# SparkFun_AzureWave_Module_Thing_Plus_AW-.net
KiCad netlist of a schematic drawn in EAGLE
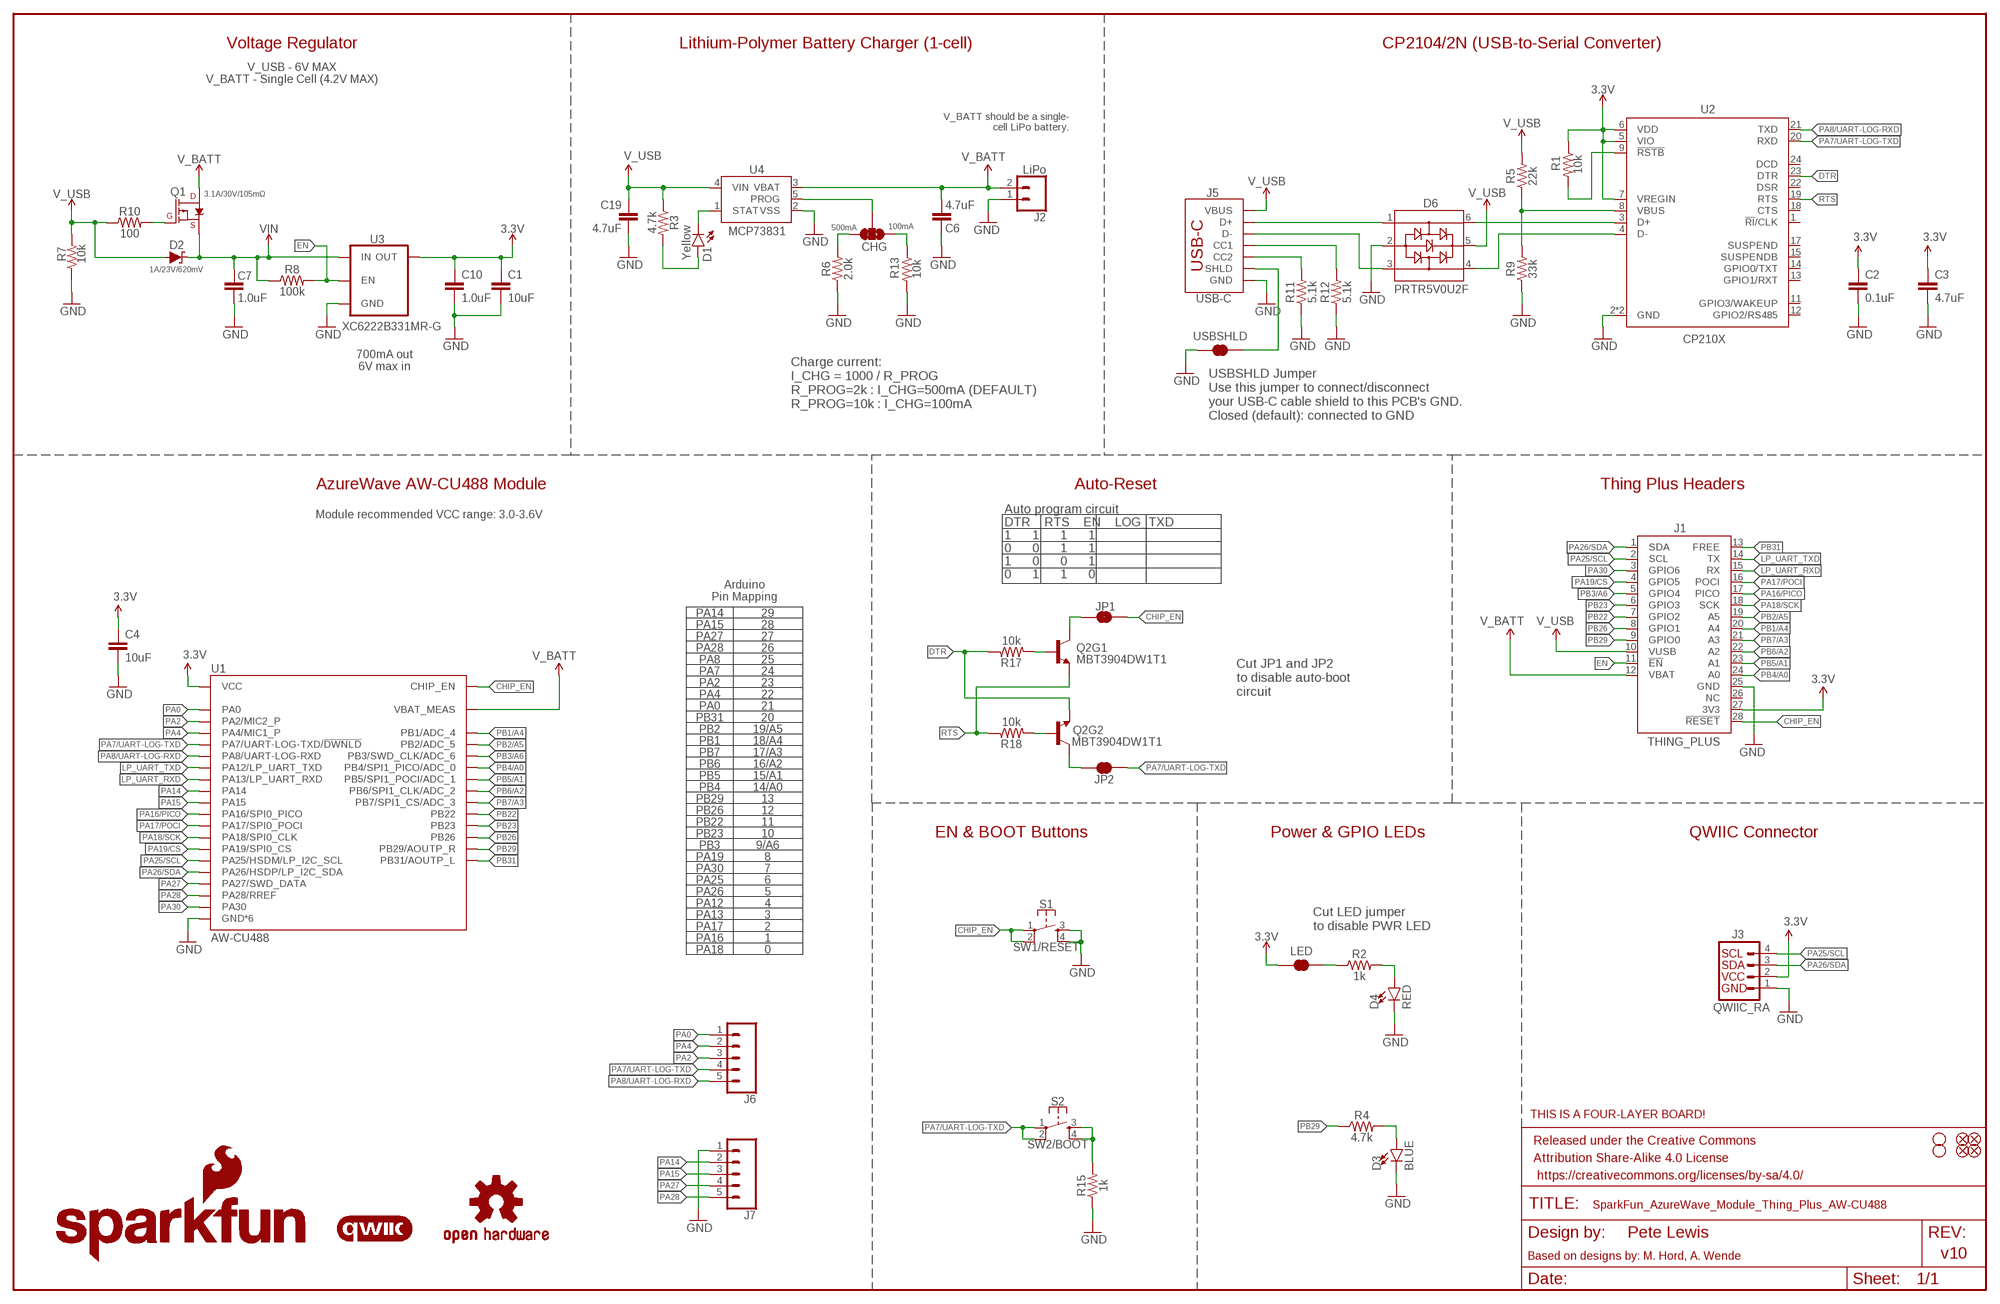
[diagram p0: schematic, sheet 1]

(export (version "E")
  (design (tool "Eeschema 10.0.6"))
  (components
    (comp (ref "C1")
      (value "10uF")
      (footprint "eagle-import:0402-TIGHT")
      (libsource (lib "eagle-import") (part "10UF-0402T-6.3V-20%"))
    )
    (comp (ref "C2")
      (value "0.1uF")
      (footprint "eagle-import:0402-TIGHT")
      (libsource (lib "eagle-import") (part "0.1UF-0402T-16V-10%"))
    )
    (comp (ref "C3")
      (value "4.7uF")
      (footprint "eagle-import:0402-TIGHT")
      (libsource (lib "eagle-import") (part "4.7UF-0402_TIGHT-6.3V-20%-X5R"))
    )
    (comp (ref "C4")
      (value "10uF")
      (footprint "eagle-import:0603")
      (libsource (lib "eagle-import") (part "10UF-0603-6.3V-20%"))
    )
    (comp (ref "C6")
      (value "4.7uF")
      (footprint "eagle-import:0402-TIGHT")
      (libsource (lib "eagle-import") (part "4.7UF-0402_TIGHT-6.3V-20%-X5R"))
    )
    (comp (ref "C7")
      (value "1.0uF")
      (footprint "eagle-import:0402-TIGHT")
      (libsource (lib "eagle-import") (part "1.0UF-0402T-16V-10%"))
    )
    (comp (ref "C10")
      (value "1.0uF")
      (footprint "eagle-import:0402-TIGHT")
      (libsource (lib "eagle-import") (part "1.0UF-0402T-16V-10%"))
    )
    (comp (ref "C19")
      (value "4.7uF")
      (footprint "eagle-import:0402-TIGHT")
      (libsource (lib "eagle-import") (part "4.7UF-0402_TIGHT-6.3V-20%-X5R"))
    )
    (comp (ref "CHG")
      (value "JUMPER-SMT_3_1-NC_TRACE_SILK")
      (footprint "eagle-import:SMT-JUMPER_3_1-NC_TRACE_SILK")
      (libsource (lib "eagle-import") (part "JUMPER-SMT_3_1-NC_TRACE_SILK"))
    )
    (comp (ref "D1")
      (value "Yellow")
      (footprint "eagle-import:LED-0603")
      (libsource (lib "eagle-import") (part "LED-YELLOW0603"))
    )
    (comp (ref "D2")
      (value "1A/23V/620mV")
      (footprint "eagle-import:SOD-323")
      (libsource (lib "eagle-import") (part "DIODE-SCHOTTKY-BAT20J"))
    )
    (comp (ref "D3")
      (value "BLUE")
      (footprint "eagle-import:LED-0603")
      (libsource (lib "eagle-import") (part "LED-BLUE0603"))
    )
    (comp (ref "D4")
      (value "RED")
      (footprint "eagle-import:LED-0603")
      (libsource (lib "eagle-import") (part "LED-RED0603"))
    )
    (comp (ref "D6")
      (value "PRTR5V0U2F")
      (footprint "eagle-import:SOT886")
      (libsource (lib "eagle-import") (part "PRTR5V0U2F"))
    )
    (comp (ref "FD1")
      (value "FIDUCIALUFIDUCIAL")
      (footprint "eagle-import:FIDUCIAL-MICRO")
      (libsource (lib "eagle-import") (part "FIDUCIALUFIDUCIAL"))
    )
    (comp (ref "FD2")
      (value "FIDUCIALUFIDUCIAL")
      (footprint "eagle-import:FIDUCIAL-MICRO")
      (libsource (lib "eagle-import") (part "FIDUCIALUFIDUCIAL"))
    )
    (comp (ref "FD3")
      (value "FIDUCIALUFIDUCIAL")
      (footprint "eagle-import:FIDUCIAL-MICRO")
      (libsource (lib "eagle-import") (part "FIDUCIALUFIDUCIAL"))
    )
    (comp (ref "FD4")
      (value "FIDUCIALUFIDUCIAL")
      (footprint "eagle-import:FIDUCIAL-MICRO")
      (libsource (lib "eagle-import") (part "FIDUCIALUFIDUCIAL"))
    )
    (comp (ref "FRAME1")
      (value "FRAME-LEDGER")
      (footprint "eagle-import:CREATIVE_COMMONS")
      (libsource (lib "eagle-import") (part "FRAME-LEDGER"))
    )
    (comp (ref "H1")
      (value "STAND-OFF")
      (footprint "eagle-import:STAND-OFF")
      (libsource (lib "eagle-import") (part "STAND-OFF"))
    )
    (comp (ref "H2")
      (value "STAND-OFF")
      (footprint "eagle-import:STAND-OFF")
      (libsource (lib "eagle-import") (part "STAND-OFF"))
    )
    (comp (ref "J1")
      (value "THING_PLUS")
      (footprint "eagle-import:THING_PLUS")
      (libsource (lib "eagle-import") (part "THING_PLUS"))
    )
    (comp (ref "J2")
      (value "LiPo")
      (footprint "eagle-import:JST-2-SMD")
      (libsource (lib "eagle-import") (part "CONN_02-JST-2MM-SMT"))
    )
    (comp (ref "J3")
      (value "QWIIC_RA")
      (footprint "eagle-import:JST04_1MM_RA")
      (libsource (lib "eagle-import") (part "QWIIC_CONNECTORJS-1MM"))
    )
    (comp (ref "J5")
      (value "USB-C")
      (footprint "eagle-import:USB-C-16P-4LAYER-ISOLATED")
      (libsource (lib "eagle-import") (part "USB_C_4-LAYER-ISOLATED"))
    )
    (comp (ref "J6")
      (value "CONN_05NO_SILK")
      (footprint "eagle-import:1X05_NO_SILK")
      (libsource (lib "eagle-import") (part "CONN_05NO_SILK"))
    )
    (comp (ref "J7")
      (value "CONN_05NO_SILK")
      (footprint "eagle-import:1X05_NO_SILK")
      (libsource (lib "eagle-import") (part "CONN_05NO_SILK"))
    )
    (comp (ref "JP1")
      (value "JUMPER-SMT_2_NC_TRACE_SILK")
      (footprint "eagle-import:SMT-JUMPER_2_NC_TRACE_SILK")
      (libsource (lib "eagle-import") (part "JUMPER-SMT_2_NC_TRACE_SILK"))
    )
    (comp (ref "JP2")
      (value "JUMPER-SMT_2_NC_TRACE_SILK")
      (footprint "eagle-import:SMT-JUMPER_2_NC_TRACE_SILK")
      (libsource (lib "eagle-import") (part "JUMPER-SMT_2_NC_TRACE_SILK"))
    )
    (comp (ref "LED")
      (value "JUMPER-SMT_2_NC_TRACE_SILK")
      (footprint "eagle-import:SMT-JUMPER_2_NC_TRACE_SILK")
      (libsource (lib "eagle-import") (part "JUMPER-SMT_2_NC_TRACE_SILK"))
    )
    (comp (ref "LOGO1")
      (value "SFE_LOGO_NAME.1_INCH")
      (footprint "eagle-import:SFE_LOGO_NAME_.1")
      (libsource (lib "eagle-import") (part "SFE_LOGO_NAME.1_INCH"))
    )
    (comp (ref "LOGO2")
      (value "OSHW-LOGOMINI")
      (footprint "eagle-import:OSHW-LOGO-MINI")
      (libsource (lib "eagle-import") (part "OSHW-LOGOMINI"))
    )
    (comp (ref "LOGO3")
      (value "SFE_LOGO_NAME_FLAME.1_INCH")
      (footprint "eagle-import:SFE_LOGO_NAME_FLAME_.1")
      (libsource (lib "eagle-import") (part "SFE_LOGO_NAME_FLAME.1_INCH"))
    )
    (comp (ref "LOGO4")
      (value "FOUR_LAYER_WARNING")
      (footprint "eagle-import:FOUR_LAYER_WARNING")
      (libsource (lib "eagle-import") (part "FOUR_LAYER_WARNING"))
    )
    (comp (ref "LOGO6")
      (value "QWIIC_LOGO_4MM")
      (footprint "eagle-import:QWIIC_4MM")
      (libsource (lib "eagle-import") (part "QWIIC_LOGO_4MM"))
    )
    (comp (ref "Q1")
      (value "3.1A/30V/105mΩ")
      (footprint "eagle-import:SOT23-3")
      (libsource (lib "eagle-import") (part "MOSFET_PCH-DMG2307L"))
    )
    (comp (ref "Q2")
      (value "MBT3904DW1T1")
      (footprint "eagle-import:SC70-6")
      (libsource (lib "eagle-import") (part "TRANS_NPN_DUAL-MBT3904DW1T1"))
    )
    (comp (ref "R1")
      (value "10k")
      (footprint "eagle-import:0402-TIGHT")
      (libsource (lib "eagle-import") (part "10KOHM-0402T-1/16W-1%"))
    )
    (comp (ref "R2")
      (value "1k")
      (footprint "eagle-import:0402-TIGHT")
      (libsource (lib "eagle-import") (part "1KOHM-0402T-1/16W-1%"))
    )
    (comp (ref "R3")
      (value "4.7k")
      (footprint "eagle-import:0402-TIGHT")
      (libsource (lib "eagle-import") (part "4.7KOHM-0402T-1/16W-1%"))
    )
    (comp (ref "R4")
      (value "4.7k")
      (footprint "eagle-import:0402-TIGHT")
      (libsource (lib "eagle-import") (part "4.7KOHM-0402T-1/16W-1%"))
    )
    (comp (ref "R5")
      (value "22k")
      (footprint "eagle-import:0402-TIGHT")
      (libsource (lib "eagle-import") (part "22KOHM-0402_TIGHT-1/10W-1%"))
    )
    (comp (ref "R6")
      (value "2.0k")
      (footprint "eagle-import:0603")
      (libsource (lib "eagle-import") (part "2.0KOHM-0603-1/10W-5%"))
    )
    (comp (ref "R7")
      (value "10k")
      (footprint "eagle-import:0402-TIGHT")
      (libsource (lib "eagle-import") (part "10KOHM-0402T-1/16W-1%"))
    )
    (comp (ref "R8")
      (value "100k")
      (footprint "eagle-import:0402-TIGHT")
      (libsource (lib "eagle-import") (part "100KOHM-0402T-1/16W-1%"))
    )
    (comp (ref "R9")
      (value "33k")
      (footprint "eagle-import:0402-TIGHT")
      (libsource (lib "eagle-import") (part "33KOHM-0402T-1/16W-1%"))
    )
    (comp (ref "R10")
      (value "100")
      (footprint "eagle-import:0402-TIGHT")
      (libsource (lib "eagle-import") (part "100OHM-0402-TIGHT-1/16W-1%"))
    )
    (comp (ref "R11")
      (value "5.1k")
      (footprint "eagle-import:0402-TIGHT")
      (libsource (lib "eagle-import") (part "5.1KOHM-0402T-1/16W-1%"))
    )
    (comp (ref "R12")
      (value "5.1k")
      (footprint "eagle-import:0402-TIGHT")
      (libsource (lib "eagle-import") (part "5.1KOHM-0402T-1/16W-1%"))
    )
    (comp (ref "R13")
      (value "10k")
      (footprint "eagle-import:0402-TIGHT")
      (libsource (lib "eagle-import") (part "10KOHM-0402T-1/16W-1%"))
    )
    (comp (ref "R15")
      (value "1k")
      (footprint "eagle-import:0402-TIGHT")
      (libsource (lib "eagle-import") (part "1KOHM-0402T-1/16W-1%"))
    )
    (comp (ref "R17")
      (value "10k")
      (footprint "eagle-import:0402-TIGHT")
      (libsource (lib "eagle-import") (part "10KOHM-0402T-1/16W-1%"))
    )
    (comp (ref "R18")
      (value "10k")
      (footprint "eagle-import:0402-TIGHT")
      (libsource (lib "eagle-import") (part "10KOHM-0402T-1/16W-1%"))
    )
    (comp (ref "S1")
      (value "SW1/RESET")
      (footprint "eagle-import:TACTILE_SWITCH_SMD_4.6X2.8MM")
      (libsource (lib "eagle-import") (part "MOMENTARY-SWITCH-SPST-2-SMD-4.6X2.8MM"))
    )
    (comp (ref "S2")
      (value "SW2/BOOT")
      (footprint "eagle-import:TACTILE_SWITCH_SMD_4.6X2.8MM")
      (libsource (lib "eagle-import") (part "MOMENTARY-SWITCH-SPST-2-SMD-4.6X2.8MM"))
    )
    (comp (ref "U1")
      (value "AW-CU488")
      (footprint "eagle-import:LGA150_AW-CU488")
      (libsource (lib "eagle-import") (part "AW-CU488LGA150"))
    )
    (comp (ref "U2")
      (value "CP210X")
      (footprint "eagle-import:QFN24")
      (libsource (lib "eagle-import") (part "CP2102N"))
    )
    (comp (ref "U3")
      (value "XC6222B331MR-G")
      (footprint "eagle-import:SOT23-5")
      (libsource (lib "eagle-import") (part "XC6222B331MR-G"))
    )
    (comp (ref "U4")
      (value "MCP73831")
      (footprint "eagle-import:SOT23-5")
      (libsource (lib "eagle-import") (part "MCP73831"))
    )
    (comp (ref "USBSHLD")
      (value "JUMPER-SMT_2_NC_TRACE_SILK")
      (footprint "eagle-import:SMT-JUMPER_2_NC_TRACE_SILK")
      (libsource (lib "eagle-import") (part "JUMPER-SMT_2_NC_TRACE_SILK"))
    )
  )
  (nets
    (net (code "1") (name "3.3V") (class "Default")
      (node (ref "C1") (pin "1") (pinfunction "1_1") (pintype "passive"))
      (node (ref "C10") (pin "1") (pinfunction "1_1") (pintype "passive"))
      (node (ref "C2") (pin "1") (pinfunction "1_1") (pintype "passive"))
      (node (ref "C3") (pin "1") (pinfunction "1_1") (pintype "passive"))
      (node (ref "C4") (pin "1") (pinfunction "1_1") (pintype "passive"))
      (node (ref "J1") (pin "27") (pinfunction "3V3_27") (pintype "bidirectional"))
      (node (ref "J3") (pin "2") (pinfunction "2_2") (pintype "power_in"))
      (node (ref "LED") (pin "1") (pinfunction "1_1") (pintype "passive"))
      (node (ref "R1") (pin "1") (pinfunction "1_1") (pintype "passive"))
      (node (ref "U1") (pin "F1") (pinfunction "VCC_F1") (pintype "bidirectional"))
      (node (ref "U2") (pin "5") (pinfunction "VIO_5") (pintype "bidirectional"))
      (node (ref "U2") (pin "6") (pinfunction "VDD_6") (pintype "bidirectional"))
      (node (ref "U2") (pin "7") (pinfunction "VREGIN_7") (pintype "bidirectional"))
      (node (ref "U3") (pin "5") (pinfunction "OUT_5") (pintype "passive"))
    )
    (net (code "2") (name "CHIP_EN") (class "Default")
      (node (ref "J1") (pin "28") (pinfunction "~{RESET}_28") (pintype "bidirectional"))
      (node (ref "JP1") (pin "2") (pinfunction "2_2") (pintype "passive"))
      (node (ref "S1") (pin "1") (pinfunction "1_1") (pintype "passive"))
      (node (ref "S1") (pin "2") (pinfunction "2_2") (pintype "passive"))
      (node (ref "U1") (pin "K11") (pinfunction "CHIP_EN_K11") (pintype "bidirectional"))
    )
    (net (code "3") (name "DTR") (class "Default")
      (node (ref "Q2") (pin "1") (pinfunction "E_1") (pintype "passive"))
      (node (ref "R17") (pin "1") (pinfunction "1_1") (pintype "passive"))
      (node (ref "U2") (pin "23") (pinfunction "DTR_23") (pintype "bidirectional"))
    )
    (net (code "4") (name "EN") (class "Default")
      (node (ref "J1") (pin "11") (pinfunction "~{EN}_11") (pintype "bidirectional"))
      (node (ref "R8") (pin "2") (pinfunction "2_2") (pintype "passive"))
      (node (ref "U3") (pin "3") (pinfunction "EN_3") (pintype "input"))
    )
    (net (code "5") (name "GND") (class "Default")
      (node (ref "C1") (pin "2") (pinfunction "2_2") (pintype "passive"))
      (node (ref "C10") (pin "2") (pinfunction "2_2") (pintype "passive"))
      (node (ref "C19") (pin "2") (pinfunction "2_2") (pintype "passive"))
      (node (ref "C2") (pin "2") (pinfunction "2_2") (pintype "passive"))
      (node (ref "C3") (pin "2") (pinfunction "2_2") (pintype "passive"))
      (node (ref "C4") (pin "2") (pinfunction "2_2") (pintype "passive"))
      (node (ref "C6") (pin "2") (pinfunction "2_2") (pintype "passive"))
      (node (ref "C7") (pin "2") (pinfunction "2_2") (pintype "passive"))
      (node (ref "D3") (pin "C") (pinfunction "C_C") (pintype "passive"))
      (node (ref "D4") (pin "C") (pinfunction "C_C") (pintype "passive"))
      (node (ref "D6") (pin "2") (pinfunction "2_2") (pintype "power_in"))
      (node (ref "J1") (pin "25") (pinfunction "GND_25") (pintype "bidirectional"))
      (node (ref "J2") (pin "1") (pinfunction "2_1") (pintype "passive"))
      (node (ref "J3") (pin "1") (pinfunction "1_1") (pintype "power_in"))
      (node (ref "J5") (pin "GND") (pinfunction "GND_GND") (pintype "bidirectional"))
      (node (ref "J5") (pin "GND2") (pinfunction "GND_GND2") (pintype "bidirectional"))
      (node (ref "J7") (pin "1") (pinfunction "1_1") (pintype "passive"))
      (node (ref "R11") (pin "1") (pinfunction "1_1") (pintype "passive"))
      (node (ref "R12") (pin "1") (pinfunction "1_1") (pintype "passive"))
      (node (ref "R13") (pin "2") (pinfunction "2_2") (pintype "passive"))
      (node (ref "R15") (pin "1") (pinfunction "1_1") (pintype "passive"))
      (node (ref "R6") (pin "1") (pinfunction "1_1") (pintype "passive"))
      (node (ref "R7") (pin "1") (pinfunction "1_1") (pintype "passive"))
      (node (ref "R9") (pin "1") (pinfunction "1_1") (pintype "passive"))
      (node (ref "S1") (pin "3") (pinfunction "3_3") (pintype "passive"))
      (node (ref "S1") (pin "4") (pinfunction "4_4") (pintype "passive"))
      (node (ref "U1") (pin "A1") (pinfunction "GND*6_A1") (pintype "bidirectional"))
      (node (ref "U1") (pin "A14") (pinfunction "GND*6_A14") (pintype "bidirectional"))
      (node (ref "U1") (pin "A15") (pinfunction "GND*6_A15") (pintype "bidirectional"))
      (node (ref "U1") (pin "A2") (pinfunction "GND*6_A2") (pintype "bidirectional"))
      (node (ref "U1") (pin "B14") (pinfunction "GND*6_B14") (pintype "bidirectional"))
      (node (ref "U1") (pin "B15") (pinfunction "GND*6_B15") (pintype "bidirectional"))
      (node (ref "U1") (pin "C10") (pinfunction "GND*6_C10") (pintype "bidirectional"))
      (node (ref "U1") (pin "C11") (pinfunction "GND*6_C11") (pintype "bidirectional"))
      (node (ref "U1") (pin "C12") (pinfunction "GND*6_C12") (pintype "bidirectional"))
      (node (ref "U1") (pin "C13") (pinfunction "GND*6_C13") (pintype "bidirectional"))
      (node (ref "U1") (pin "C14") (pinfunction "GND*6_C14") (pintype "bidirectional"))
      (node (ref "U1") (pin "C15") (pinfunction "GND*6_C15") (pintype "bidirectional"))
      (node (ref "U1") (pin "C3") (pinfunction "GND*6_C3") (pintype "bidirectional"))
      (node (ref "U1") (pin "C4") (pinfunction "GND*6_C4") (pintype "bidirectional"))
      (node (ref "U1") (pin "C5") (pinfunction "GND*6_C5") (pintype "bidirectional"))
      (node (ref "U1") (pin "C6") (pinfunction "GND*6_C6") (pintype "bidirectional"))
      (node (ref "U1") (pin "C7") (pinfunction "GND*6_C7") (pintype "bidirectional"))
      (node (ref "U1") (pin "C8") (pinfunction "GND*6_C8") (pintype "bidirectional"))
      (node (ref "U1") (pin "C9") (pinfunction "GND*6_C9") (pintype "bidirectional"))
      (node (ref "U1") (pin "D10") (pinfunction "GND*6_D10") (pintype "bidirectional"))
      (node (ref "U1") (pin "D11") (pinfunction "GND*6_D11") (pintype "bidirectional"))
      (node (ref "U1") (pin "D12") (pinfunction "GND*6_D12") (pintype "bidirectional"))
      (node (ref "U1") (pin "D13") (pinfunction "GND*6_D13") (pintype "bidirectional"))
      (node (ref "U1") (pin "D14") (pinfunction "GND*6_D14") (pintype "bidirectional"))
      (node (ref "U1") (pin "D15") (pinfunction "GND*6_D15") (pintype "bidirectional"))
      (node (ref "U1") (pin "D3") (pinfunction "GND*6_D3") (pintype "bidirectional"))
      (node (ref "U1") (pin "D4") (pinfunction "GND*6_D4") (pintype "bidirectional"))
      (node (ref "U1") (pin "D5") (pinfunction "GND*6_D5") (pintype "bidirectional"))
      (node (ref "U1") (pin "D6") (pinfunction "GND*6_D6") (pintype "bidirectional"))
      (node (ref "U1") (pin "D7") (pinfunction "GND*6_D7") (pintype "bidirectional"))
      (node (ref "U1") (pin "D8") (pinfunction "GND*6_D8") (pintype "bidirectional"))
      (node (ref "U1") (pin "D9") (pinfunction "GND*6_D9") (pintype "bidirectional"))
      (node (ref "U1") (pin "E1") (pinfunction "GND*6_E1") (pintype "bidirectional"))
      (node (ref "U1") (pin "E10") (pinfunction "GND*6_E10") (pintype "bidirectional"))
      (node (ref "U1") (pin "E11") (pinfunction "GND*6_E11") (pintype "bidirectional"))
      (node (ref "U1") (pin "E12") (pinfunction "GND*6_E12") (pintype "bidirectional"))
      (node (ref "U1") (pin "E13") (pinfunction "GND*6_E13") (pintype "bidirectional"))
      (node (ref "U1") (pin "E14") (pinfunction "GND*6_E14") (pintype "bidirectional"))
      (node (ref "U1") (pin "E15") (pinfunction "GND*6_E15") (pintype "bidirectional"))
      (node (ref "U1") (pin "E2") (pinfunction "GND*6_E2") (pintype "bidirectional"))
      (node (ref "U1") (pin "E3") (pinfunction "GND*6_E3") (pintype "bidirectional"))
      (node (ref "U1") (pin "E4") (pinfunction "GND*6_E4") (pintype "bidirectional"))
      (node (ref "U1") (pin "E5") (pinfunction "GND*6_E5") (pintype "bidirectional"))
      (node (ref "U1") (pin "E6") (pinfunction "GND*6_E6") (pintype "bidirectional"))
      (node (ref "U1") (pin "E7") (pinfunction "GND*6_E7") (pintype "bidirectional"))
      (node (ref "U1") (pin "E8") (pinfunction "GND*6_E8") (pintype "bidirectional"))
      (node (ref "U1") (pin "E9") (pinfunction "GND*6_E9") (pintype "bidirectional"))
      (node (ref "U1") (pin "F10") (pinfunction "GND*6_F10") (pintype "bidirectional"))
      (node (ref "U1") (pin "F11") (pinfunction "GND*6_F11") (pintype "bidirectional"))
      (node (ref "U1") (pin "F12") (pinfunction "GND*6_F12") (pintype "bidirectional"))
      (node (ref "U1") (pin "F13") (pinfunction "GND*6_F13") (pintype "bidirectional"))
      (node (ref "U1") (pin "F14") (pinfunction "GND*6_F14") (pintype "bidirectional"))
      (node (ref "U1") (pin "F15") (pinfunction "GND*6_F15") (pintype "bidirectional"))
      (node (ref "U1") (pin "F2") (pinfunction "GND*6_F2") (pintype "bidirectional"))
      (node (ref "U1") (pin "F3") (pinfunction "GND*6_F3") (pintype "bidirectional"))
      (node (ref "U1") (pin "F4") (pinfunction "GND*6_F4") (pintype "bidirectional"))
      (node (ref "U1") (pin "F5") (pinfunction "GND*6_F5") (pintype "bidirectional"))
      (node (ref "U1") (pin "F6") (pinfunction "GND*6_F6") (pintype "bidirectional"))
      (node (ref "U1") (pin "F7") (pinfunction "GND*6_F7") (pintype "bidirectional"))
      (node (ref "U1") (pin "F8") (pinfunction "GND*6_F8") (pintype "bidirectional"))
      (node (ref "U1") (pin "F9") (pinfunction "GND*6_F9") (pintype "bidirectional"))
      (node (ref "U1") (pin "G1") (pinfunction "GND*6_G1") (pintype "bidirectional"))
      (node (ref "U1") (pin "G10") (pinfunction "GND*6_G10") (pintype "bidirectional"))
      (node (ref "U1") (pin "G11") (pinfunction "GND*6_G11") (pintype "bidirectional"))
      (node (ref "U1") (pin "G12") (pinfunction "GND*6_G12") (pintype "bidirectional"))
      (node (ref "U1") (pin "G13") (pinfunction "GND*6_G13") (pintype "bidirectional"))
      (node (ref "U1") (pin "G14") (pinfunction "GND*6_G14") (pintype "bidirectional"))
      (node (ref "U1") (pin "G15") (pinfunction "GND*6_G15") (pintype "bidirectional"))
      (node (ref "U1") (pin "G2") (pinfunction "GND*6_G2") (pintype "bidirectional"))
      (node (ref "U1") (pin "G3") (pinfunction "GND*6_G3") (pintype "bidirectional"))
      (node (ref "U1") (pin "G4") (pinfunction "GND*6_G4") (pintype "bidirectional"))
      (node (ref "U1") (pin "G5") (pinfunction "GND*6_G5") (pintype "bidirectional"))
      (node (ref "U1") (pin "G6") (pinfunction "GND*6_G6") (pintype "bidirectional"))
      (node (ref "U1") (pin "G7") (pinfunction "GND*6_G7") (pintype "bidirectional"))
      (node (ref "U1") (pin "G8") (pinfunction "GND*6_G8") (pintype "bidirectional"))
      (node (ref "U1") (pin "G9") (pinfunction "GND*6_G9") (pintype "bidirectional"))
      (node (ref "U1") (pin "H10") (pinfunction "GND*6_H10") (pintype "bidirectional"))
      (node (ref "U1") (pin "H11") (pinfunction "GND*6_H11") (pintype "bidirectional"))
      (node (ref "U1") (pin "H12") (pinfunction "GND*6_H12") (pintype "bidirectional"))
      (node (ref "U1") (pin "H13") (pinfunction "GND*6_H13") (pintype "bidirectional"))
      (node (ref "U1") (pin "H14") (pinfunction "GND*6_H14") (pintype "bidirectional"))
      (node (ref "U1") (pin "H15") (pinfunction "GND*6_H15") (pintype "bidirectional"))
      (node (ref "U1") (pin "H3") (pinfunction "GND*6_H3") (pintype "bidirectional"))
      (node (ref "U1") (pin "H4") (pinfunction "GND*6_H4") (pintype "bidirectional"))
      (node (ref "U1") (pin "H5") (pinfunction "GND*6_H5") (pintype "bidirectional"))
      (node (ref "U1") (pin "H6") (pinfunction "GND*6_H6") (pintype "bidirectional"))
      (node (ref "U1") (pin "H7") (pinfunction "GND*6_H7") (pintype "bidirectional"))
      (node (ref "U1") (pin "H8") (pinfunction "GND*6_H8") (pintype "bidirectional"))
      (node (ref "U1") (pin "H9") (pinfunction "GND*6_H9") (pintype "bidirectional"))
      (node (ref "U1") (pin "J14") (pinfunction "GND*6_J14") (pintype "bidirectional"))
      (node (ref "U1") (pin "J15") (pinfunction "GND*6_J15") (pintype "bidirectional"))
      (node (ref "U1") (pin "K14") (pinfunction "GND*6_K14") (pintype "bidirectional"))
      (node (ref "U1") (pin "K15") (pinfunction "GND*6_K15") (pintype "bidirectional"))
      (node (ref "U1") (pin "K3") (pinfunction "GND*6_K3") (pintype "bidirectional"))
      (node (ref "U1") (pin "K4") (pinfunction "GND*6_K4") (pintype "bidirectional"))
      (node (ref "U2") (pin "2") (pinfunction "GND_2") (pintype "bidirectional"))
      (node (ref "U2") (pin "PAD") (pinfunction "GND_PAD") (pintype "bidirectional"))
      (node (ref "U3") (pin "2") (pinfunction "GND_2") (pintype "input"))
      (node (ref "U4") (pin "2") (pinfunction "VSS_2") (pintype "power_in"))
      (node (ref "USBSHLD") (pin "1") (pinfunction "1_1") (pintype "passive"))
    )
    (net (code "6") (name "LP_UART_RXD") (class "Default")
      (node (ref "J1") (pin "15") (pinfunction "RX_15") (pintype "bidirectional"))
      (node (ref "U1") (pin "B13") (pinfunction "PA13/LP_UART_RXD_B13") (pintype "bidirectional"))
    )
    (net (code "7") (name "LP_UART_TXD") (class "Default")
      (node (ref "J1") (pin "14") (pinfunction "TX_14") (pintype "bidirectional"))
      (node (ref "U1") (pin "A13") (pinfunction "PA12/LP_UART_TXD_A13") (pintype "bidirectional"))
    )
    (net (code "8") (name "Net-(CHG-Pad1)") (class "Default")
      (node (ref "CHG") (pin "1") (pinfunction "1_1") (pintype "passive"))
      (node (ref "R13") (pin "1") (pinfunction "1_1") (pintype "passive"))
    )
    (net (code "9") (name "Net-(CHG-Pad3)") (class "Default")
      (node (ref "CHG") (pin "3") (pinfunction "3_3") (pintype "passive"))
      (node (ref "R6") (pin "2") (pinfunction "2_2") (pintype "passive"))
    )
    (net (code "10") (name "Net-(D1-PadA)") (class "Default")
      (node (ref "D1") (pin "A") (pinfunction "A_A") (pintype "passive"))
      (node (ref "R3") (pin "2") (pinfunction "2_2") (pintype "passive"))
    )
    (net (code "11") (name "Net-(D3-PadA)") (class "Default")
      (node (ref "D3") (pin "A") (pinfunction "A_A") (pintype "passive"))
      (node (ref "R4") (pin "2") (pinfunction "2_2") (pintype "passive"))
    )
    (net (code "12") (name "Net-(D4-PadA)") (class "Default")
      (node (ref "D4") (pin "A") (pinfunction "A_A") (pintype "passive"))
      (node (ref "R2") (pin "2") (pinfunction "2_2") (pintype "passive"))
    )
    (net (code "13") (name "Net-(D6-Pad1)") (class "Default")
      (node (ref "D6") (pin "1") (pinfunction "1_1") (pintype "bidirectional"))
      (node (ref "J5") (pin "A6") (pinfunction "D+_A6") (pintype "bidirectional"))
      (node (ref "J5") (pin "B6") (pinfunction "D+_B6") (pintype "bidirectional"))
    )
    (net (code "14") (name "Net-(D6-Pad3)") (class "Default")
      (node (ref "D6") (pin "3") (pinfunction "3_3") (pintype "bidirectional"))
      (node (ref "J5") (pin "A7") (pinfunction "D-_A7") (pintype "bidirectional"))
      (node (ref "J5") (pin "B7") (pinfunction "D-_B7") (pintype "bidirectional"))
    )
    (net (code "15") (name "Net-(J5-CC1)") (class "Default")
      (node (ref "J5") (pin "A5") (pinfunction "CC1_A5") (pintype "bidirectional"))
      (node (ref "R12") (pin "2") (pinfunction "2_2") (pintype "passive"))
    )
    (net (code "16") (name "Net-(J5-CC2)") (class "Default")
      (node (ref "J5") (pin "B5") (pinfunction "CC2_B5") (pintype "bidirectional"))
      (node (ref "R11") (pin "2") (pinfunction "2_2") (pintype "passive"))
    )
    (net (code "17") (name "Net-(J5-SHLD-PadSHLD1)") (class "Default")
      (node (ref "J5") (pin "SHLD1") (pinfunction "SHLD_SHLD1") (pintype "bidirectional"))
      (node (ref "J5") (pin "SHLD2") (pinfunction "SHLD_SHLD2") (pintype "bidirectional"))
      (node (ref "J5") (pin "SHLD3") (pinfunction "SHLD_SHLD3") (pintype "bidirectional"))
      (node (ref "J5") (pin "SHLD4") (pinfunction "SHLD_SHLD4") (pintype "bidirectional"))
      (node (ref "J5") (pin "SHLD5") (pinfunction "SHLD_SHLD5") (pintype "bidirectional"))
      (node (ref "J5") (pin "SHLD6") (pinfunction "SHLD_SHLD6") (pintype "bidirectional"))
      (node (ref "J5") (pin "SHLD7") (pinfunction "SHLD_SHLD7") (pintype "bidirectional"))
      (node (ref "J5") (pin "SHLD8") (pinfunction "SHLD_SHLD8") (pintype "bidirectional"))
      (node (ref "USBSHLD") (pin "2") (pinfunction "2_2") (pintype "passive"))
    )
    (net (code "18") (name "Net-(LED-Pad2)") (class "Default")
      (node (ref "LED") (pin "2") (pinfunction "2_2") (pintype "passive"))
      (node (ref "R2") (pin "1") (pinfunction "1_1") (pintype "passive"))
    )
    (net (code "19") (name "Net-(Q1-G)") (class "Default")
      (node (ref "Q1") (pin "1") (pinfunction "G_1") (pintype "bidirectional"))
      (node (ref "R10") (pin "2") (pinfunction "2_2") (pintype "passive"))
    )
    (net (code "20") (name "Net-(Q2A-B)") (class "Default")
      (node (ref "Q2") (pin "5") (pinfunction "B_5") (pintype "passive"))
      (node (ref "R17") (pin "2") (pinfunction "2_2") (pintype "passive"))
    )
    (net (code "21") (name "Net-(Q2A-C)") (class "Default")
      (node (ref "JP1") (pin "1") (pinfunction "1_1") (pintype "passive"))
      (node (ref "Q2") (pin "3") (pinfunction "C_3") (pintype "passive"))
    )
    (net (code "22") (name "Net-(Q2B-B)") (class "Default")
      (node (ref "Q2") (pin "2") (pinfunction "B_2") (pintype "passive"))
      (node (ref "R18") (pin "2") (pinfunction "2_2") (pintype "passive"))
    )
    (net (code "23") (name "Net-(Q2B-C)") (class "Default")
      (node (ref "JP2") (pin "1") (pinfunction "1_1") (pintype "passive"))
      (node (ref "Q2") (pin "6") (pinfunction "C_6") (pintype "passive"))
    )
    (net (code "24") (name "Net-(R15-Pad2)") (class "Default")
      (node (ref "R15") (pin "2") (pinfunction "2_2") (pintype "passive"))
      (node (ref "S2") (pin "3") (pinfunction "3_3") (pintype "passive"))
      (node (ref "S2") (pin "4") (pinfunction "4_4") (pintype "passive"))
    )
    (net (code "25") (name "Net-(U2-D+)") (class "Default")
      (node (ref "D6") (pin "6") (pinfunction "6_6") (pintype "bidirectional"))
      (node (ref "U2") (pin "3") (pinfunction "D+_3") (pintype "bidirectional"))
    )
    (net (code "26") (name "Net-(U2-D-)") (class "Default")
      (node (ref "D6") (pin "4") (pinfunction "4_4") (pintype "bidirectional"))
      (node (ref "U2") (pin "4") (pinfunction "D-_4") (pintype "bidirectional"))
    )
    (net (code "27") (name "Net-(U2-VBUS)") (class "Default")
      (node (ref "R5") (pin "1") (pinfunction "1_1") (pintype "passive"))
      (node (ref "R9") (pin "2") (pinfunction "2_2") (pintype "passive"))
      (node (ref "U2") (pin "8") (pinfunction "VBUS_8") (pintype "bidirectional"))
    )
    (net (code "28") (name "Net-(U2-~{RSTB})") (class "Default")
      (node (ref "R1") (pin "2") (pinfunction "2_2") (pintype "passive"))
      (node (ref "U2") (pin "9") (pinfunction "~{RSTB}_9") (pintype "bidirectional"))
    )
    (net (code "29") (name "Net-(U4-PROG)") (class "Default")
      (node (ref "CHG") (pin "2") (pinfunction "2_2") (pintype "passive"))
      (node (ref "U4") (pin "5") (pinfunction "PROG_5") (pintype "input"))
    )
    (net (code "30") (name "Net-(U4-STAT)") (class "Default")
      (node (ref "D1") (pin "C") (pinfunction "C_C") (pintype "passive"))
      (node (ref "U4") (pin "1") (pinfunction "STAT_1") (pintype "output"))
    )
    (net (code "31") (name "PA0") (class "Default")
      (node (ref "J6") (pin "1") (pinfunction "1_1") (pintype "passive"))
      (node (ref "U1") (pin "K8") (pinfunction "PA0_K8") (pintype "bidirectional"))
    )
    (net (code "32") (name "PA2") (class "Default")
      (node (ref "J6") (pin "3") (pinfunction "3_3") (pintype "passive"))
      (node (ref "U1") (pin "K10") (pinfunction "PA2/MIC2_P_K10") (pintype "bidirectional"))
    )
    (net (code "33") (name "PA4") (class "Default")
      (node (ref "J6") (pin "2") (pinfunction "2_2") (pintype "passive"))
      (node (ref "U1") (pin "K9") (pinfunction "PA4/MIC1_P_K9") (pintype "bidirectional"))
    )
    (net (code "34") (name "PA7{slash}UART-LOG-TXD") (class "Default")
      (node (ref "J6") (pin "4") (pinfunction "4_4") (pintype "passive"))
      (node (ref "JP2") (pin "2") (pinfunction "2_2") (pintype "passive"))
      (node (ref "S2") (pin "1") (pinfunction "1_1") (pintype "passive"))
      (node (ref "S2") (pin "2") (pinfunction "2_2") (pintype "passive"))
      (node (ref "U1") (pin "K12") (pinfunction "PA7/UART-LOG-TXD/~{DWNLD}_K12") (pintype "bidirectional"))
      (node (ref "U2") (pin "20") (pinfunction "RXD_20") (pintype "bidirectional"))
    )
    (net (code "35") (name "PA8{slash}UART-LOG-RXD") (class "Default")
      (node (ref "J6") (pin "5") (pinfunction "5_5") (pintype "passive"))
      (node (ref "U1") (pin "K13") (pinfunction "PA8/UART-LOG-RXD_K13") (pintype "bidirectional"))
      (node (ref "U2") (pin "21") (pinfunction "TXD_21") (pintype "bidirectional"))
    )
    (net (code "36") (name "PA14") (class "Default")
      (node (ref "J7") (pin "2") (pinfunction "2_2") (pintype "passive"))
      (node (ref "U1") (pin "A12") (pinfunction "PA14_A12") (pintype "bidirectional"))
    )
    (net (code "37") (name "PA15") (class "Default")
      (node (ref "J7") (pin "3") (pinfunction "3_3") (pintype "passive"))
      (node (ref "U1") (pin "B12") (pinfunction "PA15_B12") (pintype "bidirectional"))
    )
    (net (code "38") (name "PA16{slash}PICO") (class "Default")
      (node (ref "J1") (pin "17") (pinfunction "PICO_17") (pintype "bidirectional"))
      (node (ref "U1") (pin "A11") (pinfunction "PA16/SPI0_PICO_A11") (pintype "bidirectional"))
    )
    (net (code "39") (name "PA17{slash}POCI") (class "Default")
      (node (ref "J1") (pin "16") (pinfunction "POCI_16") (pintype "bidirectional"))
      (node (ref "U1") (pin "B11") (pinfunction "PA17/SPI0_POCI_B11") (pintype "bidirectional"))
    )
    (net (code "40") (name "PA18{slash}SCK") (class "Default")
      (node (ref "J1") (pin "18") (pinfunction "SCK_18") (pintype "bidirectional"))
      (node (ref "U1") (pin "A10") (pinfunction "PA18/SPI0_CLK_A10") (pintype "bidirectional"))
    )
    (net (code "41") (name "PA19{slash}CS") (class "Default")
      (node (ref "J1") (pin "4") (pinfunction "GPIO5_4") (pintype "bidirectional"))
      (node (ref "U1") (pin "B10") (pinfunction "PA19/SPI0_CS_B10") (pintype "bidirectional"))
    )
    (net (code "42") (name "PA25{slash}SCL") (class "Default")
      (node (ref "J1") (pin "2") (pinfunction "SCL_2") (pintype "bidirectional"))
      (node (ref "J3") (pin "4") (pinfunction "4_4") (pintype "passive"))
      (node (ref "U1") (pin "A5") (pinfunction "PA25/HSDM/LP_I2C_SCL_A5") (pintype "bidirectional"))
    )
    (net (code "43") (name "PA26{slash}SDA") (class "Default")
      (node (ref "J1") (pin "1") (pinfunction "SDA_1") (pintype "bidirectional"))
      (node (ref "J3") (pin "3") (pinfunction "3_3") (pintype "passive"))
      (node (ref "U1") (pin "A6") (pinfunction "PA26/HSDP/LP_I2C_SDA_A6") (pintype "bidirectional"))
    )
    (net (code "44") (name "PA27") (class "Default")
      (node (ref "J7") (pin "4") (pinfunction "4_4") (pintype "passive"))
      (node (ref "U1") (pin "A9") (pinfunction "PA27/SWD_DATA_A9") (pintype "bidirectional"))
    )
    (net (code "45") (name "PA28") (class "Default")
      (node (ref "J7") (pin "5") (pinfunction "5_5") (pintype "passive"))
      (node (ref "U1") (pin "A7") (pinfunction "PA28/RREF_A7") (pintype "bidirectional"))
    )
    (net (code "46") (name "PA30") (class "Default")
      (node (ref "J1") (pin "3") (pinfunction "GPIO6_3") (pintype "bidirectional"))
      (node (ref "U1") (pin "A8") (pinfunction "PA30_A8") (pintype "bidirectional"))
    )
    (net (code "47") (name "PB1{slash}A4") (class "Default")
      (node (ref "J1") (pin "20") (pinfunction "A4_20") (pintype "bidirectional"))
      (node (ref "U1") (pin "A3") (pinfunction "PB1/ADC_4_A3") (pintype "bidirectional"))
    )
    (net (code "48") (name "PB2{slash}A5") (class "Default")
      (node (ref "J1") (pin "19") (pinfunction "A5_19") (pintype "bidirectional"))
      (node (ref "U1") (pin "A4") (pinfunction "PB2/ADC_5_A4") (pintype "bidirectional"))
    )
    (net (code "49") (name "PB3{slash}A6") (class "Default")
      (node (ref "J1") (pin "5") (pinfunction "GPIO4_5") (pintype "bidirectional"))
      (node (ref "U1") (pin "B1") (pinfunction "PB3/SWD_CLK/ADC_6_B1") (pintype "bidirectional"))
    )
    (net (code "50") (name "PB4{slash}A0") (class "Default")
      (node (ref "J1") (pin "24") (pinfunction "A0_24") (pintype "bidirectional"))
      (node (ref "U1") (pin "B2") (pinfunction "PB4/SPI1_PICO/ADC_0_B2") (pintype "bidirectional"))
    )
    (net (code "51") (name "PB5{slash}A1") (class "Default")
      (node (ref "J1") (pin "23") (pinfunction "A1_23") (pintype "bidirectional"))
      (node (ref "U1") (pin "C1") (pinfunction "PB5/SPI1_POCI/ADC_1_C1") (pintype "bidirectional"))
    )
    (net (code "52") (name "PB6{slash}A2") (class "Default")
      (node (ref "J1") (pin "22") (pinfunction "A2_22") (pintype "bidirectional"))
      (node (ref "U1") (pin "C2") (pinfunction "PB6/SPI1_CLK/ADC_2_C2") (pintype "bidirectional"))
    )
    (net (code "53") (name "PB7{slash}A3") (class "Default")
      (node (ref "J1") (pin "21") (pinfunction "A3_21") (pintype "bidirectional"))
      (node (ref "U1") (pin "D1") (pinfunction "PB7/SPI1_CS/ADC_3_D1") (pintype "bidirectional"))
    )
    (net (code "54") (name "PB22") (class "Default")
      (node (ref "J1") (pin "7") (pinfunction "GPIO2_7") (pintype "bidirectional"))
      (node (ref "U1") (pin "K1") (pinfunction "PB22_K1") (pintype "bidirectional"))
    )
    (net (code "55") (name "PB23") (class "Default")
      (node (ref "J1") (pin "6") (pinfunction "GPIO3_6") (pintype "bidirectional"))
      (node (ref "U1") (pin "K2") (pinfunction "PB23_K2") (pintype "bidirectional"))
    )
    (net (code "56") (name "PB26") (class "Default")
      (node (ref "J1") (pin "8") (pinfunction "GPIO1_8") (pintype "bidirectional"))
      (node (ref "U1") (pin "K5") (pinfunction "PB26_K5") (pintype "bidirectional"))
    )
    (net (code "57") (name "PB29") (class "Default")
      (node (ref "J1") (pin "9") (pinfunction "GPIO0_9") (pintype "bidirectional"))
      (node (ref "R4") (pin "1") (pinfunction "1_1") (pintype "passive"))
      (node (ref "U1") (pin "K6") (pinfunction "PB29/AOUTP_R_K6") (pintype "bidirectional"))
    )
    (net (code "58") (name "PB31") (class "Default")
      (node (ref "J1") (pin "13") (pinfunction "FREE_13") (pintype "bidirectional"))
      (node (ref "U1") (pin "K7") (pinfunction "PB31/AOUTP_L_K7") (pintype "bidirectional"))
    )
    (net (code "59") (name "RTS") (class "Default")
      (node (ref "Q2") (pin "4") (pinfunction "E_4") (pintype "passive"))
      (node (ref "R18") (pin "1") (pinfunction "1_1") (pintype "passive"))
      (node (ref "U2") (pin "19") (pinfunction "RTS_19") (pintype "bidirectional"))
    )
    (net (code "60") (name "VIN") (class "Default")
      (node (ref "C7") (pin "1") (pinfunction "1_1") (pintype "passive"))
      (node (ref "D2") (pin "C") (pinfunction "C_C") (pintype "passive"))
      (node (ref "Q1") (pin "2") (pinfunction "S_2") (pintype "bidirectional"))
      (node (ref "R8") (pin "1") (pinfunction "1_1") (pintype "passive"))
      (node (ref "U3") (pin "1") (pinfunction "IN_1") (pintype "input"))
    )
    (net (code "61") (name "V_BATT") (class "Default")
      (node (ref "C6") (pin "1") (pinfunction "1_1") (pintype "passive"))
      (node (ref "J1") (pin "12") (pinfunction "VBAT_12") (pintype "bidirectional"))
      (node (ref "J2") (pin "2") (pinfunction "1_2") (pintype "passive"))
      (node (ref "Q1") (pin "3") (pinfunction "D_3") (pintype "bidirectional"))
      (node (ref "U1") (pin "D2") (pinfunction "VBAT_MEAS_D2") (pintype "bidirectional"))
      (node (ref "U4") (pin "3") (pinfunction "VBAT_3") (pintype "power_in"))
    )
    (net (code "62") (name "V_USB") (class "Default")
      (node (ref "C19") (pin "1") (pinfunction "1_1") (pintype "passive"))
      (node (ref "D2") (pin "A") (pinfunction "A_A") (pintype "passive"))
      (node (ref "D6") (pin "5") (pinfunction "5_5") (pintype "power_in"))
      (node (ref "J1") (pin "10") (pinfunction "VUSB_10") (pintype "bidirectional"))
      (node (ref "J5") (pin "VBUS1") (pinfunction "VBUS_VBUS1") (pintype "bidirectional"))
      (node (ref "J5") (pin "VBUS2") (pinfunction "VBUS_VBUS2") (pintype "bidirectional"))
      (node (ref "R10") (pin "1") (pinfunction "1_1") (pintype "passive"))
      (node (ref "R3") (pin "1") (pinfunction "1_1") (pintype "passive"))
      (node (ref "R5") (pin "2") (pinfunction "2_2") (pintype "passive"))
      (node (ref "R7") (pin "2") (pinfunction "2_2") (pintype "passive"))
      (node (ref "U4") (pin "4") (pinfunction "VIN_4") (pintype "power_in"))
    )
    (net (code "63") (name "unconnected-(J1-NC-Pad26)") (class "Default")
      (node (ref "J1") (pin "26") (pinfunction "NC_26") (pintype "bidirectional"))
    )
    (net (code "64") (name "unconnected-(U2-CTS-Pad18)") (class "Default")
      (node (ref "U2") (pin "18") (pinfunction "CTS_18") (pintype "bidirectional"))
    )
    (net (code "65") (name "unconnected-(U2-DCD-Pad24)") (class "Default")
      (node (ref "U2") (pin "24") (pinfunction "DCD_24") (pintype "bidirectional"))
    )
    (net (code "66") (name "unconnected-(U2-DSR-Pad22)") (class "Default")
      (node (ref "U2") (pin "22") (pinfunction "DSR_22") (pintype "bidirectional"))
    )
    (net (code "67") (name "unconnected-(U2-GPIO0{slash}TXT-Pad14)") (class "Default")
      (node (ref "U2") (pin "14") (pinfunction "GPIO0/TXT_14") (pintype "bidirectional"))
    )
    (net (code "68") (name "unconnected-(U2-GPIO1{slash}RXT-Pad13)") (class "Default")
      (node (ref "U2") (pin "13") (pinfunction "GPIO1/RXT_13") (pintype "bidirectional"))
    )
    (net (code "69") (name "unconnected-(U2-GPIO2{slash}RS485-Pad12)") (class "Default")
      (node (ref "U2") (pin "12") (pinfunction "GPIO2/RS485_12") (pintype "bidirectional"))
    )
    (net (code "70") (name "unconnected-(U2-GPIO3{slash}WAKEUP-Pad11)") (class "Default")
      (node (ref "U2") (pin "11") (pinfunction "GPIO3/WAKEUP_11") (pintype "bidirectional"))
    )
    (net (code "71") (name "unconnected-(U2-SUSPEND-Pad17)") (class "Default")
      (node (ref "U2") (pin "17") (pinfunction "SUSPEND_17") (pintype "bidirectional"))
    )
    (net (code "72") (name "unconnected-(U2-SUSPENDB-Pad15)") (class "Default")
      (node (ref "U2") (pin "15") (pinfunction "SUSPENDB_15") (pintype "bidirectional"))
    )
    (net (code "73") (name "unconnected-(U2-~{RI}{slash}CLK-Pad1)") (class "Default")
      (node (ref "U2") (pin "1") (pinfunction "~{RI}/CLK_1") (pintype "bidirectional"))
    )
  )
)
